# 20.net
KiCad netlist of a schematic drawn in Altium Designer
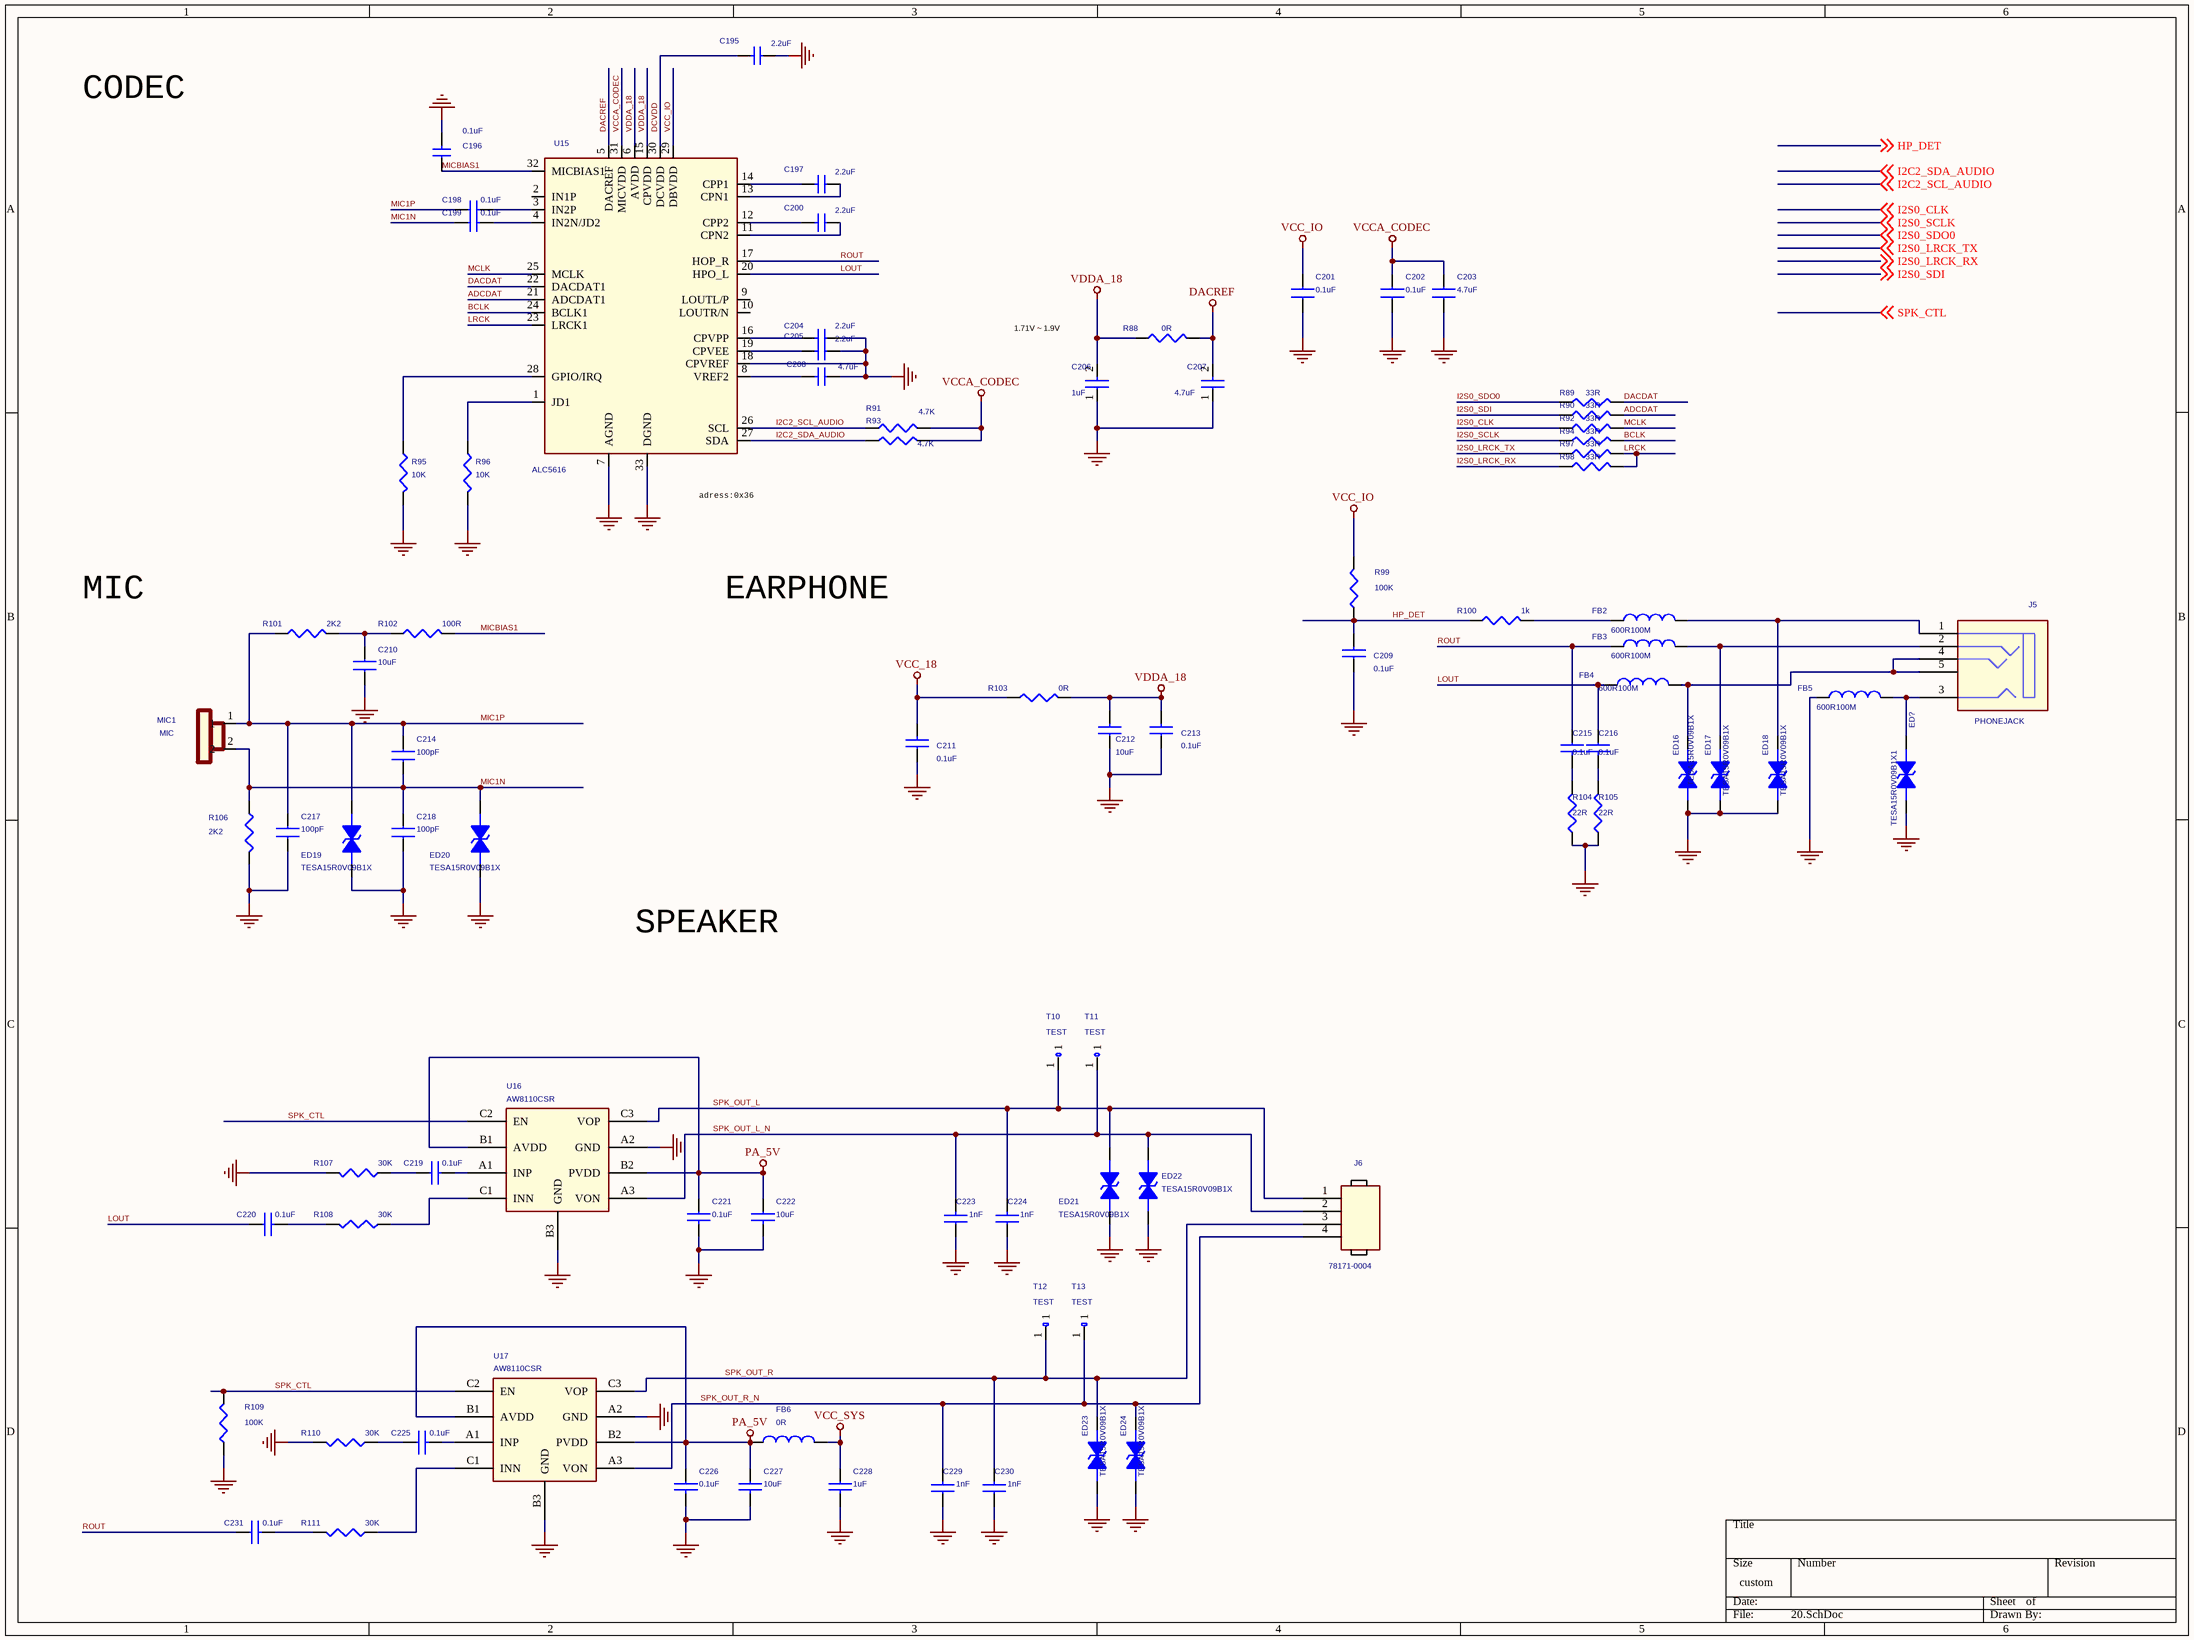
[diagram p0: 20.SchDoc]

(export (version "E")
  (design (tool "Eeschema 10.0.6"))
  (components
    (comp (ref "C195")
      (value "2.2uF")
      (footprint "C0603")
      (description "RoHS CHIP CAP 2.2uF +10/-10% X5R")
      (libsource (lib "*") (part "SMALL CAP"))
    )
    (comp (ref "C196")
      (value "0.1uF")
      (footprint "c0402")
      (description "RoHS CHIP CAP 0.1uF +10/-10% X7R")
      (libsource (lib "*") (part "SMALL CAP"))
    )
    (comp (ref "C197")
      (value "2.2uF")
      (footprint "C0603")
      (description "RoHS CHIP CAP 2.2uF +10/-10% X5R")
      (libsource (lib "*") (part "SMALL CAP"))
    )
    (comp (ref "C198")
      (value "0.1uF")
      (footprint "c0402")
      (description "RoHS CHIP CAP 0.1uF +10/-10% X7R")
      (libsource (lib "*") (part "SMALL CAP"))
    )
    (comp (ref "C199")
      (value "0.1uF")
      (footprint "c0402")
      (description "RoHS CHIP CAP 0.1uF +10/-10% X7R")
      (libsource (lib "*") (part "SMALL CAP"))
    )
    (comp (ref "C200")
      (value "2.2uF")
      (footprint "C0603")
      (description "RoHS CHIP CAP 2.2uF +10/-10% X5R")
      (libsource (lib "*") (part "SMALL CAP"))
    )
    (comp (ref "C201")
      (value "0.1uF")
      (footprint "C0603")
      (description "RoHS CHIP CAP 0.1uF +10/-10% X7R")
      (libsource (lib "*") (part "CAP NP_Dup3"))
    )
    (comp (ref "C202")
      (value "0.1uF")
      (footprint "C0603")
      (description "RoHS CHIP CAP 0.1uF +10/-10% X7R")
      (libsource (lib "*") (part "CAP NP_Dup3"))
    )
    (comp (ref "C203")
      (value "4.7uF")
      (footprint "C0603")
      (description "RoHS CHIP CAP 2.2uF +10/-10% X5R")
      (libsource (lib "*") (part "CAP NP_Dup3"))
    )
    (comp (ref "C204")
      (value "2.2uF")
      (footprint "C0603")
      (description "RoHS CHIP CAP 2.2uF +10/-10% X5R")
      (libsource (lib "*") (part "SMALL CAP"))
    )
    (comp (ref "C205")
      (value "2.2uF")
      (footprint "C0603")
      (description "RoHS CHIP CAP 2.2uF +10/-10% X5R")
      (libsource (lib "*") (part "SMALL CAP"))
    )
    (comp (ref "C206")
      (value "1uF")
      (footprint "c0402")
      (description "RoHS CHIP CAP 4.7uF +10/-10% X5R")
      (libsource (lib "*") (part "CAP NP_0"))
    )
    (comp (ref "C207")
      (value "4.7uF")
      (footprint "C0603")
      (description "RoHS CHIP CAP 4.7uF +10/-10% X5R")
      (libsource (lib "*") (part "CAP NP_0"))
    )
    (comp (ref "C208")
      (value "4.7uF")
      (footprint "C0603")
      (description "RoHS CHIP CAP 4.7uF +10/-10% X5R")
      (libsource (lib "*") (part "SMALL CAP"))
    )
    (comp (ref "C209") (value "0.1uF") (footprint "c0402") (libsource (lib "*") (part "CAP NP_4")))
    (comp (ref "C210") (value "10uF") (footprint "C0603") (libsource (lib "*") (part "CAP NP_Dup3")))
    (comp (ref "C211") (value "0.1uF") (footprint "C0201") (libsource (lib "*") (part "CAP NP_4")))
    (comp (ref "C212") (value "10uF") (footprint "C0603") (libsource (lib "*") (part "CAP NP_4")))
    (comp (ref "C213") (value "0.1uF") (footprint "c0402") (libsource (lib "*") (part "CAP NP_4")))
    (comp (ref "C214")
      (value "100pF")
      (footprint "C0603")
      (description "RoHS CHIP CAP 100pF +10/-10% X7R")
      (libsource (lib "*") (part "CAP NP_Dup3"))
    )
    (comp (ref "C215")
      (value "0.1uF")
      (footprint "c0402")
      (description "RoHS CHIP CAP 0.1uF +10/-10% X7R")
      (libsource (lib "*") (part "CAP NP_Dup1"))
    )
    (comp (ref "C216")
      (value "0.1uF")
      (footprint "c0402")
      (description "RoHS CHIP CAP 0.1uF +10/-10% X7R")
      (libsource (lib "*") (part "CAP NP_Dup1"))
    )
    (comp (ref "C217")
      (value "100pF")
      (footprint "C0603")
      (description "RoHS CHIP CAP 100pF +10/-10% X7R")
      (libsource (lib "*") (part "CAP NP_Dup3"))
    )
    (comp (ref "C218")
      (value "100pF")
      (footprint "C0603")
      (description "RoHS CHIP CAP 100pF +10/-10% X7R")
      (libsource (lib "*") (part "CAP NP_Dup3"))
    )
    (comp (ref "C219")
      (value "0.1uF")
      (footprint "C0402")
      (description "RoHS CHIP CAP 0.1uF +10/-10% X7R")
      (libsource (lib "*") (part "CAP NP_Dup2"))
    )
    (comp (ref "C220")
      (value "0.1uF")
      (footprint "C0402")
      (description "RoHS CHIP CAP 0.1uF +10/-10% X7R")
      (libsource (lib "*") (part "CAP NP_Dup2"))
    )
    (comp (ref "C221")
      (value "0.1uF")
      (footprint "C0402")
      (description "RoHS CHIP CAP 0.1uF +10/-10% X7R")
      (libsource (lib "*") (part "CAP NP_Dup2"))
    )
    (comp (ref "C222")
      (value "10uF")
      (footprint "C0402")
      (description "RoHS CHIP CAP 10uF +10/-10% X5R")
      (libsource (lib "*") (part "CAP NP_Dup2"))
    )
    (comp (ref "C223")
      (value "1nF")
      (footprint "C0402")
      (description "RoHS CHIP CAP 1nF +10/-10% X7R")
      (libsource (lib "*") (part "CAP NP_Dup2"))
    )
    (comp (ref "C224")
      (value "1nF")
      (footprint "C0402")
      (description "RoHS CHIP CAP 1nF +10/-10% X7R")
      (libsource (lib "*") (part "CAP NP_Dup2"))
    )
    (comp (ref "C225")
      (value "0.1uF")
      (footprint "C0402")
      (description "RoHS CHIP CAP 0.1uF +10/-10% X7R")
      (libsource (lib "*") (part "CAP NP_Dup2"))
    )
    (comp (ref "C226")
      (value "0.1uF")
      (footprint "C0402")
      (description "RoHS CHIP CAP 0.1uF +10/-10% X7R")
      (libsource (lib "*") (part "CAP NP_Dup2"))
    )
    (comp (ref "C227")
      (value "10uF")
      (footprint "C0402")
      (description "RoHS CHIP CAP 10uF +10/-10% X5R")
      (libsource (lib "*") (part "CAP NP_Dup2"))
    )
    (comp (ref "C228")
      (value "1uF")
      (footprint "C0402")
      (description "RoHS CHIP CAP 10uF +10/-10% X5R")
      (libsource (lib "*") (part "CAP NP_Dup2"))
    )
    (comp (ref "C229")
      (value "1nF")
      (footprint "C0402")
      (description "RoHS CHIP CAP 1nF +10/-10% X7R")
      (libsource (lib "*") (part "CAP NP_Dup2"))
    )
    (comp (ref "C230")
      (value "1nF")
      (footprint "C0402")
      (description "RoHS CHIP CAP 1nF +10/-10% X7R")
      (libsource (lib "*") (part "CAP NP_Dup2"))
    )
    (comp (ref "C231")
      (value "0.1uF")
      (footprint "C0402")
      (description "RoHS CHIP CAP 0.1uF +10/-10% X7R")
      (libsource (lib "*") (part "CAP NP_Dup2"))
    )
    (comp (ref "ED16")
      (value "TESA15R0V09B1X")
      (footprint "E0402N")
      (description "ESD Component,5V,30P,SMD,0402")
      (libsource (lib "*") (part "TVS"))
    )
    (comp (ref "ED17")
      (value "TESA15R0V09B1X")
      (footprint "E0402N")
      (description "ESD Component,5V,30P,SMD,0402")
      (libsource (lib "*") (part "TVS"))
    )
    (comp (ref "ED18")
      (value "TESA15R0V09B1X")
      (footprint "E0402N")
      (description "ESD Component,5V,30P,SMD,0402")
      (libsource (lib "*") (part "TVS"))
    )
    (comp (ref "ED19")
      (value "TESA15R0V09B1X")
      (footprint "E0201")
      (description "NC/ESD Component,5V,30P,SMD,0402")
      (libsource (lib "*") (part "DIODE BI-DIR TRIG"))
    )
    (comp (ref "ED20")
      (value "TESA15R0V09B1X")
      (footprint "E0201")
      (description "NC/ESD Component,5V,30P,SMD,0402")
      (libsource (lib "*") (part "DIODE BI-DIR TRIG"))
    )
    (comp (ref "ED21")
      (value "TESA15R0V09B1X")
      (footprint "E0201")
      (description "NC/ESD Component,5V,30P,SMD,0402")
      (libsource (lib "*") (part "DIODE BI-DIR TRIG"))
    )
    (comp (ref "ED22")
      (value "TESA15R0V09B1X")
      (footprint "E0201")
      (description "NC/ESD Component,5V,30P,SMD,0402")
      (libsource (lib "*") (part "DIODE BI-DIR TRIG"))
    )
    (comp (ref "ED23")
      (value "TESA15R0V09B1X")
      (footprint "E0402N")
      (description "ESD Component,5V,30P,SMD,0402")
      (libsource (lib "*") (part "TVS"))
    )
    (comp (ref "ED24")
      (value "TESA15R0V09B1X")
      (footprint "E0402N")
      (description "ESD Component,5V,30P,SMD,0402")
      (libsource (lib "*") (part "TVS"))
    )
    (comp (ref "FB2")
      (value "600R100M")
      (footprint "L0402")
      (description "ROHS CHIP RES 33R 1/16W 5%")
      (libsource (lib "*") (part "INDUCTOR_Dup1"))
    )
    (comp (ref "FB3")
      (value "600R100M")
      (footprint "L0402")
      (description "ROHS CHIP RES 33R 1/16W 5%")
      (libsource (lib "*") (part "INDUCTOR_Dup1"))
    )
    (comp (ref "FB4")
      (value "600R100M")
      (footprint "L0402")
      (description "ROHS CHIP RES 33R 1/16W 5%")
      (libsource (lib "*") (part "INDUCTOR_Dup1"))
    )
    (comp (ref "FB5")
      (value "600R100M")
      (footprint "L0402")
      (description "ROHS CHIP RES 33R 1/16W 5%")
      (libsource (lib "*") (part "INDUCTOR_Dup1"))
    )
    (comp (ref "FB6")
      (value "0R")
      (footprint "L0603")
      (description "ROHS CHIP RES 0 Ohm 1/16W +/-5%")
      (libsource (lib "*") (part "INDUCTOR_Dup1"))
    )
    (comp (ref "J5")
      (value "PHONEJACK")
      (footprint "J301R05GA6ZL2")
      (description "耳插")
      (libsource (lib "*") (part "PHONEJACK STEREO SW_0"))
    )
    (comp (ref "J6") (value "78171-0004") (footprint "78171-0004") (libsource (lib "*") (part "HEADER 4")))
    (comp (ref "MIC1") (value "MIC") (footprint "78171-0002") (libsource (lib "*") (part "MIC")))
    (comp (ref "R88")
      (value "0R")
      (footprint "R0402")
      (description "ROHS CHIP RES 0 Ohm 1/16W +/-5%")
      (libsource (lib "*") (part "R"))
    )
    (comp (ref "R89")
      (value "33R")
      (footprint "r0402")
      (description "ROHS CHIP RES 33 Ohm 1/16W +/-5%")
      (libsource (lib "*") (part "R"))
    )
    (comp (ref "R90")
      (value "33R")
      (footprint "r0402")
      (description "ROHS CHIP RES 33 Ohm 1/16W +/-5%")
      (libsource (lib "*") (part "R"))
    )
    (comp (ref "R91")
      (value "4.7K")
      (footprint "r0402")
      (description "ROHS CHIP RES 0 Ohm 1/16W +/-5%")
      (libsource (lib "*") (part "R"))
    )
    (comp (ref "R92")
      (value "33R")
      (footprint "r0402")
      (description "ROHS CHIP RES 33 Ohm 1/16W +/-5%")
      (libsource (lib "*") (part "R"))
    )
    (comp (ref "R93")
      (value "4.7K")
      (footprint "r0402")
      (description "ROHS CHIP RES 0 Ohm 1/16W +/-5%")
      (libsource (lib "*") (part "R"))
    )
    (comp (ref "R94")
      (value "33R")
      (footprint "r0402")
      (description "ROHS CHIP RES 33 Ohm 1/16W +/-5%")
      (libsource (lib "*") (part "R"))
    )
    (comp (ref "R95")
      (value "10K")
      (footprint "r0402")
      (description "ROHS CHIP RES 10K 1/16W +/-5%")
      (libsource (lib "*") (part "RESISTOR"))
    )
    (comp (ref "R96")
      (value "10K")
      (footprint "r0402")
      (description "ROHS CHIP RES 10K 1/16W +/-5%")
      (libsource (lib "*") (part "RESISTOR"))
    )
    (comp (ref "R97")
      (value "33R")
      (footprint "r0402")
      (description "ROHS CHIP RES 33 Ohm 1/16W +/-5%")
      (libsource (lib "*") (part "R"))
    )
    (comp (ref "R98")
      (value "33R")
      (footprint "r0402")
      (description "ROHS CHIP RES 33 Ohm 1/16W +/-5%")
      (libsource (lib "*") (part "R"))
    )
    (comp (ref "R99")
      (value "100K")
      (footprint "r0402")
      (description "RES,thick film,10KOhm,+/-5%,1/16W,SMD0402")
      (libsource (lib "*") (part "RESISTOR_1_Dup2"))
    )
    (comp (ref "R100")
      (value "1k")
      (footprint "r0402")
      (description "RES,thick film,10KOhm,+/-5%,1/16W,SMD0402")
      (libsource (lib "*") (part "RESISTOR_1_Dup2"))
    )
    (comp (ref "R101") (value "2K2") (footprint "r0402") (libsource (lib "*") (part "RESISTOR_0_Dup2")))
    (comp (ref "R102")
      (value "100R")
      (footprint "r0402")
      (description "RES,thick film,10KOhm,+/-5%,1/16W,SMD0402")
      (libsource (lib "*") (part "RESISTOR_1_Dup2"))
    )
    (comp (ref "R103")
      (value "0R")
      (footprint "R0402")
      (description "ROHS CHIP RES 0R 1/16W 5%")
      (libsource (lib "*") (part "RESISTOR"))
    )
    (comp (ref "R104")
      (value "22R")
      (footprint "r0402")
      (description "ROHS CHIP RES 22R 1/16W 5%")
      (libsource (lib "*") (part "RESISTOR"))
    )
    (comp (ref "R105")
      (value "22R")
      (footprint "r0402")
      (description "ROHS CHIP RES 22R 1/16W 5%")
      (libsource (lib "*") (part "RESISTOR"))
    )
    (comp (ref "R106")
      (value "2K2")
      (footprint "r0402")
      (description "贴片电阻")
      (libsource (lib "*") (part "RESISTOR_0_Dup2"))
    )
    (comp (ref "R107")
      (value "30K")
      (footprint "R0402")
      (description "ROHS CHIP RES 30K 1/16W +/-5%")
      (libsource (lib "*") (part "RESISTOR_Dup1"))
    )
    (comp (ref "R108")
      (value "30K")
      (footprint "R0402")
      (description "ROHS CHIP RES 30K 1/16W +/-5%")
      (libsource (lib "*") (part "RESISTOR_Dup1"))
    )
    (comp (ref "R109")
      (value "100K")
      (footprint "r0402")
      (description "RES,thick film,10KOhm,+/-5%,1/16W,SMD0402")
      (libsource (lib "*") (part "RESISTOR_1_Dup2"))
    )
    (comp (ref "R110")
      (value "30K")
      (footprint "R0402")
      (description "ROHS CHIP RES 30K 1/16W +/-5%")
      (libsource (lib "*") (part "RESISTOR_Dup1"))
    )
    (comp (ref "R111")
      (value "30K")
      (footprint "R0402")
      (description "ROHS CHIP RES 30K 1/16W +/-5%")
      (libsource (lib "*") (part "RESISTOR_Dup1"))
    )
    (comp (ref "T10") (value "TEST") (footprint "TEST") (libsource (lib "*") (part "TEST_0")))
    (comp (ref "T11") (value "TEST") (footprint "TEST") (libsource (lib "*") (part "TEST_0")))
    (comp (ref "T12") (value "TEST") (footprint "TEST") (libsource (lib "*") (part "TEST_0")))
    (comp (ref "T13") (value "TEST") (footprint "TEST") (libsource (lib "*") (part "TEST_0")))
    (comp (ref "TESA15R0V09B1X1")
      (value "ED?")
      (footprint "E0402N")
      (description "ESD Component,5V,30P,SMD,0402")
      (libsource (lib "*") (part "TVS"))
    )
    (comp (ref "U15")
      (value "ALC5616")
      (footprint "QFN32")
      (description "CODEC IC")
      (libsource (lib "*") (part "ALC5616"))
    )
    (comp (ref "U16")
      (value "AW8110CSR")
      (footprint "CSP9")
      (description "Class D Audio AMP")
      (libsource (lib "*") (part "LM4990_0"))
    )
    (comp (ref "U17")
      (value "AW8110CSR")
      (footprint "CSP9")
      (description "Class D Audio AMP")
      (libsource (lib "*") (part "LM4990_0"))
    )
  )
  (nets
    (net (code "1") (name "/ADCDAT") (class "Default")
      (node (ref "R90") (pin "2") (pinfunction "2_2") (pintype "passive"))
      (node (ref "U15") (pin "21") (pinfunction "ADCDAT1_21") (pintype "passive"))
    )
    (net (code "2") (name "/BCLK") (class "Default")
      (node (ref "R94") (pin "2") (pinfunction "2_2") (pintype "passive"))
      (node (ref "U15") (pin "24") (pinfunction "BCLK1_24") (pintype "passive"))
    )
    (net (code "3") (name "/DACDAT") (class "Default")
      (node (ref "R89") (pin "2") (pinfunction "2_2") (pintype "passive"))
      (node (ref "U15") (pin "22") (pinfunction "DACDAT1_22") (pintype "passive"))
    )
    (net (code "4") (name "/DCVDD") (class "Default")
      (node (ref "C195") (pin "2") (pinfunction "2_2") (pintype "passive"))
      (node (ref "U15") (pin "30") (pinfunction "DCVDD_30") (pintype "passive"))
    )
    (net (code "5") (name "/LOUT") (class "Default")
      (node (ref "C216") (pin "1") (pinfunction "1_1") (pintype "passive"))
      (node (ref "C220") (pin "1") (pinfunction "1_1") (pintype "passive"))
      (node (ref "FB4") (pin "2") (pinfunction "2_2") (pintype "passive"))
      (node (ref "U15") (pin "20") (pinfunction "HPO_L_20") (pintype "passive"))
    )
    (net (code "6") (name "/LRCK") (class "Default")
      (node (ref "R97") (pin "2") (pinfunction "2_2") (pintype "passive"))
      (node (ref "R98") (pin "2") (pinfunction "2_2") (pintype "passive"))
      (node (ref "U15") (pin "23") (pinfunction "LRCK1_23") (pintype "passive"))
    )
    (net (code "7") (name "/MCLK") (class "Default")
      (node (ref "R92") (pin "2") (pinfunction "2_2") (pintype "passive"))
      (node (ref "U15") (pin "25") (pinfunction "MCLK_25") (pintype "passive"))
    )
    (net (code "8") (name "/MIC1N") (class "Default")
      (node (ref "C199") (pin "1") (pinfunction "1_1") (pintype "passive"))
      (node (ref "C214") (pin "1") (pinfunction "1_1") (pintype "passive"))
      (node (ref "C218") (pin "2") (pinfunction "2_2") (pintype "passive"))
      (node (ref "ED20") (pin "1") (pinfunction "1_1") (pintype "passive"))
      (node (ref "MIC1") (pin "2") (pinfunction "2_2") (pintype "passive"))
      (node (ref "R106") (pin "2") (pinfunction "2_2") (pintype "passive"))
    )
    (net (code "9") (name "/MIC1P") (class "Default")
      (node (ref "C198") (pin "1") (pinfunction "1_1") (pintype "passive"))
      (node (ref "C214") (pin "2") (pinfunction "2_2") (pintype "passive"))
      (node (ref "C217") (pin "2") (pinfunction "2_2") (pintype "passive"))
      (node (ref "ED19") (pin "1") (pinfunction "1_1") (pintype "passive"))
      (node (ref "MIC1") (pin "1") (pinfunction "1_1") (pintype "passive"))
      (node (ref "R101") (pin "1") (pinfunction "1_1") (pintype "passive"))
    )
    (net (code "10") (name "/MICBIAS1") (class "Default")
      (node (ref "C196") (pin "1") (pinfunction "1_1") (pintype "passive"))
      (node (ref "R102") (pin "1") (pinfunction "1_1") (pintype "passive"))
      (node (ref "U15") (pin "32") (pinfunction "MICBIAS1_32") (pintype "passive"))
    )
    (net (code "11") (name "/ROUT") (class "Default")
      (node (ref "C215") (pin "1") (pinfunction "1_1") (pintype "passive"))
      (node (ref "C231") (pin "1") (pinfunction "1_1") (pintype "passive"))
      (node (ref "FB3") (pin "2") (pinfunction "2_2") (pintype "passive"))
      (node (ref "U15") (pin "17") (pinfunction "HOP_R_17") (pintype "passive"))
    )
    (net (code "12") (name "/SPK_OUT_L") (class "Default")
      (node (ref "C224") (pin "2") (pinfunction "2_2") (pintype "passive"))
      (node (ref "ED21") (pin "1") (pinfunction "1_1") (pintype "passive"))
      (node (ref "J6") (pin "1") (pinfunction "1_1") (pintype "passive"))
      (node (ref "T10") (pin "1") (pinfunction "1_1") (pintype "passive"))
      (node (ref "U16") (pin "C3") (pinfunction "VOP_C3") (pintype "passive"))
    )
    (net (code "13") (name "/SPK_OUT_L_N") (class "Default")
      (node (ref "C223") (pin "2") (pinfunction "2_2") (pintype "passive"))
      (node (ref "ED22") (pin "1") (pinfunction "1_1") (pintype "passive"))
      (node (ref "J6") (pin "2") (pinfunction "2_2") (pintype "passive"))
      (node (ref "T11") (pin "1") (pinfunction "1_1") (pintype "passive"))
      (node (ref "U16") (pin "A3") (pinfunction "VON_A3") (pintype "passive"))
    )
    (net (code "14") (name "/SPK_OUT_R") (class "Default")
      (node (ref "C230") (pin "2") (pinfunction "2_2") (pintype "passive"))
      (node (ref "ED23") (pin "1") (pinfunction "1_1") (pintype "passive"))
      (node (ref "J6") (pin "3") (pinfunction "3_3") (pintype "passive"))
      (node (ref "T12") (pin "1") (pinfunction "1_1") (pintype "passive"))
      (node (ref "U17") (pin "C3") (pinfunction "VOP_C3") (pintype "passive"))
    )
    (net (code "15") (name "/SPK_OUT_R_N") (class "Default")
      (node (ref "C229") (pin "2") (pinfunction "2_2") (pintype "passive"))
      (node (ref "ED24") (pin "1") (pinfunction "1_1") (pintype "passive"))
      (node (ref "J6") (pin "4") (pinfunction "4_4") (pintype "passive"))
      (node (ref "T13") (pin "1") (pinfunction "1_1") (pintype "passive"))
      (node (ref "U17") (pin "A3") (pinfunction "VON_A3") (pintype "passive"))
    )
    (net (code "16") (name "DACREF") (class "Default")
      (node (ref "C207") (pin "2") (pinfunction "2_2") (pintype "passive"))
      (node (ref "R88") (pin "2") (pinfunction "2_2") (pintype "passive"))
      (node (ref "U15") (pin "5") (pinfunction "DACREF_5") (pintype "passive"))
    )
    (net (code "17") (name "GND") (class "Default")
      (node (ref "C195") (pin "1") (pinfunction "1_1") (pintype "passive"))
      (node (ref "C196") (pin "2") (pinfunction "2_2") (pintype "passive"))
      (node (ref "C201") (pin "1") (pinfunction "1_1") (pintype "passive"))
      (node (ref "C202") (pin "1") (pinfunction "1_1") (pintype "passive"))
      (node (ref "C203") (pin "1") (pinfunction "1_1") (pintype "passive"))
      (node (ref "C204") (pin "1") (pinfunction "1_1") (pintype "passive"))
      (node (ref "C205") (pin "1") (pinfunction "1_1") (pintype "passive"))
      (node (ref "C206") (pin "1") (pinfunction "1_1") (pintype "passive"))
      (node (ref "C207") (pin "1") (pinfunction "1_1") (pintype "passive"))
      (node (ref "C208") (pin "1") (pinfunction "1_1") (pintype "passive"))
      (node (ref "C209") (pin "1") (pinfunction "1_1") (pintype "passive"))
      (node (ref "C210") (pin "1") (pinfunction "1_1") (pintype "passive"))
      (node (ref "C211") (pin "1") (pinfunction "1_1") (pintype "passive"))
      (node (ref "C212") (pin "1") (pinfunction "1_1") (pintype "passive"))
      (node (ref "C213") (pin "1") (pinfunction "1_1") (pintype "passive"))
      (node (ref "C217") (pin "1") (pinfunction "1_1") (pintype "passive"))
      (node (ref "C218") (pin "1") (pinfunction "1_1") (pintype "passive"))
      (node (ref "C221") (pin "2") (pinfunction "2_2") (pintype "passive"))
      (node (ref "C222") (pin "2") (pinfunction "2_2") (pintype "passive"))
      (node (ref "C223") (pin "1") (pinfunction "1_1") (pintype "passive"))
      (node (ref "C224") (pin "1") (pinfunction "1_1") (pintype "passive"))
      (node (ref "C226") (pin "2") (pinfunction "2_2") (pintype "passive"))
      (node (ref "C227") (pin "2") (pinfunction "2_2") (pintype "passive"))
      (node (ref "C228") (pin "2") (pinfunction "2_2") (pintype "passive"))
      (node (ref "C229") (pin "1") (pinfunction "1_1") (pintype "passive"))
      (node (ref "C230") (pin "1") (pinfunction "1_1") (pintype "passive"))
      (node (ref "ED16") (pin "2") (pinfunction "2_2") (pintype "passive"))
      (node (ref "ED17") (pin "2") (pinfunction "2_2") (pintype "passive"))
      (node (ref "ED18") (pin "2") (pinfunction "2_2") (pintype "passive"))
      (node (ref "ED19") (pin "2") (pinfunction "2_2") (pintype "passive"))
      (node (ref "ED20") (pin "2") (pinfunction "2_2") (pintype "passive"))
      (node (ref "ED21") (pin "2") (pinfunction "2_2") (pintype "passive"))
      (node (ref "ED22") (pin "2") (pinfunction "2_2") (pintype "passive"))
      (node (ref "ED23") (pin "2") (pinfunction "2_2") (pintype "passive"))
      (node (ref "ED24") (pin "2") (pinfunction "2_2") (pintype "passive"))
      (node (ref "FB5") (pin "2") (pinfunction "2_2") (pintype "passive"))
      (node (ref "R104") (pin "1") (pinfunction "1_1") (pintype "passive"))
      (node (ref "R105") (pin "1") (pinfunction "1_1") (pintype "passive"))
      (node (ref "R106") (pin "1") (pinfunction "1_1") (pintype "passive"))
      (node (ref "R107") (pin "2") (pinfunction "2_2") (pintype "passive"))
      (node (ref "R109") (pin "2") (pinfunction "2_2") (pintype "passive"))
      (node (ref "R110") (pin "2") (pinfunction "2_2") (pintype "passive"))
      (node (ref "R95") (pin "1") (pinfunction "1_1") (pintype "passive"))
      (node (ref "R96") (pin "1") (pinfunction "1_1") (pintype "passive"))
      (node (ref "TESA15R0V09B1X1") (pin "2") (pinfunction "2_2") (pintype "passive"))
      (node (ref "U15") (pin "18") (pinfunction "CPVREF_18") (pintype "passive"))
      (node (ref "U15") (pin "33") (pinfunction "DGND_33") (pintype "passive"))
      (node (ref "U15") (pin "7") (pinfunction "AGND_7") (pintype "passive"))
      (node (ref "U16") (pin "A2") (pinfunction "GND_A2") (pintype "power_in"))
      (node (ref "U16") (pin "B3") (pinfunction "GND_B3") (pintype "power_in"))
      (node (ref "U17") (pin "A2") (pinfunction "GND_A2") (pintype "power_in"))
      (node (ref "U17") (pin "B3") (pinfunction "GND_B3") (pintype "power_in"))
    )
    (net (code "18") (name "HP_DET") (class "Default")
      (node (ref "C209") (pin "2") (pinfunction "2_2") (pintype "passive"))
      (node (ref "R100") (pin "2") (pinfunction "2_2") (pintype "passive"))
      (node (ref "R99") (pin "2") (pinfunction "2_2") (pintype "passive"))
    )
    (net (code "19") (name "I2C2_SCL_AUDIO") (class "Default")
      (node (ref "R91") (pin "1") (pinfunction "1_1") (pintype "passive"))
      (node (ref "U15") (pin "26") (pinfunction "SCL_26") (pintype "passive"))
    )
    (net (code "20") (name "I2C2_SDA_AUDIO") (class "Default")
      (node (ref "R93") (pin "1") (pinfunction "1_1") (pintype "passive"))
      (node (ref "U15") (pin "27") (pinfunction "SDA_27") (pintype "passive"))
    )
    (net (code "21") (name "I2S0_CLK") (class "Default")
      (node (ref "R92") (pin "1") (pinfunction "1_1") (pintype "passive"))
    )
    (net (code "22") (name "I2S0_LRCK_RX") (class "Default")
      (node (ref "R98") (pin "1") (pinfunction "1_1") (pintype "passive"))
    )
    (net (code "23") (name "I2S0_LRCK_TX") (class "Default")
      (node (ref "R97") (pin "1") (pinfunction "1_1") (pintype "passive"))
    )
    (net (code "24") (name "I2S0_SCLK") (class "Default")
      (node (ref "R94") (pin "1") (pinfunction "1_1") (pintype "passive"))
    )
    (net (code "25") (name "I2S0_SDI") (class "Default")
      (node (ref "R90") (pin "1") (pinfunction "1_1") (pintype "passive"))
    )
    (net (code "26") (name "I2S0_SDO0") (class "Default")
      (node (ref "R89") (pin "1") (pinfunction "1_1") (pintype "passive"))
    )
    (net (code "27") (name "Net-(C210-Pad2)") (class "Default")
      (node (ref "C210") (pin "2") (pinfunction "2_2") (pintype "passive"))
      (node (ref "R101") (pin "2") (pinfunction "2_2") (pintype "passive"))
      (node (ref "R102") (pin "2") (pinfunction "2_2") (pintype "passive"))
    )
    (net (code "28") (name "Net-(C215-Pad2)") (class "Default")
      (node (ref "C215") (pin "2") (pinfunction "2_2") (pintype "passive"))
      (node (ref "R104") (pin "2") (pinfunction "2_2") (pintype "passive"))
    )
    (net (code "29") (name "Net-(C216-Pad2)") (class "Default")
      (node (ref "C216") (pin "2") (pinfunction "2_2") (pintype "passive"))
      (node (ref "R105") (pin "2") (pinfunction "2_2") (pintype "passive"))
    )
    (net (code "30") (name "Net-(C219-Pad1)") (class "Default")
      (node (ref "C219") (pin "1") (pinfunction "1_1") (pintype "passive"))
      (node (ref "R107") (pin "1") (pinfunction "1_1") (pintype "passive"))
    )
    (net (code "31") (name "Net-(C220-Pad2)") (class "Default")
      (node (ref "C220") (pin "2") (pinfunction "2_2") (pintype "passive"))
      (node (ref "R108") (pin "2") (pinfunction "2_2") (pintype "passive"))
    )
    (net (code "32") (name "Net-(C225-Pad1)") (class "Default")
      (node (ref "C225") (pin "1") (pinfunction "1_1") (pintype "passive"))
      (node (ref "R110") (pin "1") (pinfunction "1_1") (pintype "passive"))
    )
    (net (code "33") (name "Net-(C231-Pad2)") (class "Default")
      (node (ref "C231") (pin "2") (pinfunction "2_2") (pintype "passive"))
      (node (ref "R111") (pin "2") (pinfunction "2_2") (pintype "passive"))
    )
    (net (code "34") (name "Net-(FB2-Pad2)") (class "Default")
      (node (ref "FB2") (pin "2") (pinfunction "2_2") (pintype "passive"))
      (node (ref "R100") (pin "1") (pinfunction "1_1") (pintype "passive"))
    )
    (net (code "35") (name "Net-(J5-D)") (class "Default")
      (node (ref "ED17") (pin "1") (pinfunction "1_1") (pintype "passive"))
      (node (ref "FB3") (pin "1") (pinfunction "1_1") (pintype "passive"))
      (node (ref "J5") (pin "2") (pinfunction "D_2") (pintype "passive"))
    )
    (net (code "36") (name "Net-(J5-HP)") (class "Default")
      (node (ref "ED18") (pin "1") (pinfunction "1_1") (pintype "passive"))
      (node (ref "FB2") (pin "1") (pinfunction "1_1") (pintype "passive"))
      (node (ref "J5") (pin "1") (pinfunction "HP_1") (pintype "passive"))
    )
    (net (code "37") (name "Net-(J5-L)") (class "Default")
      (node (ref "ED16") (pin "1") (pinfunction "1_1") (pintype "passive"))
      (node (ref "FB4") (pin "1") (pinfunction "1_1") (pintype "passive"))
      (node (ref "J5") (pin "4") (pinfunction "R_4") (pintype "passive"))
      (node (ref "J5") (pin "5") (pinfunction "L_5") (pintype "passive"))
    )
    (net (code "38") (name "Net-(J5-R1)") (class "Default")
      (node (ref "FB5") (pin "1") (pinfunction "1_1") (pintype "passive"))
      (node (ref "J5") (pin "3") (pinfunction "R1_3") (pintype "passive"))
      (node (ref "TESA15R0V09B1X1") (pin "1") (pinfunction "1_1") (pintype "passive"))
    )
    (net (code "39") (name "Net-(U15-CPN1)") (class "Default")
      (node (ref "C197") (pin "1") (pinfunction "1_1") (pintype "passive"))
      (node (ref "U15") (pin "13") (pinfunction "CPN1_13") (pintype "passive"))
    )
    (net (code "40") (name "Net-(U15-CPN2)") (class "Default")
      (node (ref "C200") (pin "1") (pinfunction "1_1") (pintype "passive"))
      (node (ref "U15") (pin "11") (pinfunction "CPN2_11") (pintype "passive"))
    )
    (net (code "41") (name "Net-(U15-CPP1)") (class "Default")
      (node (ref "C197") (pin "2") (pinfunction "2_2") (pintype "passive"))
      (node (ref "U15") (pin "14") (pinfunction "CPP1_14") (pintype "passive"))
    )
    (net (code "42") (name "Net-(U15-CPP2)") (class "Default")
      (node (ref "C200") (pin "2") (pinfunction "2_2") (pintype "passive"))
      (node (ref "U15") (pin "12") (pinfunction "CPP2_12") (pintype "passive"))
    )
    (net (code "43") (name "Net-(U15-CPVEE)") (class "Default")
      (node (ref "C205") (pin "2") (pinfunction "2_2") (pintype "passive"))
      (node (ref "U15") (pin "19") (pinfunction "CPVEE_19") (pintype "passive"))
    )
    (net (code "44") (name "Net-(U15-CPVPP)") (class "Default")
      (node (ref "C204") (pin "2") (pinfunction "2_2") (pintype "passive"))
      (node (ref "U15") (pin "16") (pinfunction "CPVPP_16") (pintype "passive"))
    )
    (net (code "45") (name "Net-(U15-GPIO{slash}IRQ)") (class "Default")
      (node (ref "R95") (pin "2") (pinfunction "2_2") (pintype "passive"))
      (node (ref "U15") (pin "28") (pinfunction "GPIO/IRQ_28") (pintype "passive"))
    )
    (net (code "46") (name "Net-(U15-IN2N{slash}JD2)") (class "Default")
      (node (ref "C199") (pin "2") (pinfunction "2_2") (pintype "passive"))
      (node (ref "U15") (pin "4") (pinfunction "IN2N/JD2_4") (pintype "passive"))
    )
    (net (code "47") (name "Net-(U15-IN2P)") (class "Default")
      (node (ref "C198") (pin "2") (pinfunction "2_2") (pintype "passive"))
      (node (ref "U15") (pin "3") (pinfunction "IN2P_3") (pintype "passive"))
    )
    (net (code "48") (name "Net-(U15-JD1)") (class "Default")
      (node (ref "R96") (pin "2") (pinfunction "2_2") (pintype "passive"))
      (node (ref "U15") (pin "1") (pinfunction "JD1_1") (pintype "passive"))
    )
    (net (code "49") (name "Net-(U15-VREF2)") (class "Default")
      (node (ref "C208") (pin "2") (pinfunction "2_2") (pintype "passive"))
      (node (ref "U15") (pin "8") (pinfunction "VREF2_8") (pintype "passive"))
    )
    (net (code "50") (name "Net-(U16-INN)") (class "Default")
      (node (ref "R108") (pin "1") (pinfunction "1_1") (pintype "passive"))
      (node (ref "U16") (pin "C1") (pinfunction "INN_C1") (pintype "passive"))
    )
    (net (code "51") (name "Net-(U16-INP)") (class "Default")
      (node (ref "C219") (pin "2") (pinfunction "2_2") (pintype "passive"))
      (node (ref "U16") (pin "A1") (pinfunction "INP_A1") (pintype "passive"))
    )
    (net (code "52") (name "Net-(U17-INN)") (class "Default")
      (node (ref "R111") (pin "1") (pinfunction "1_1") (pintype "passive"))
      (node (ref "U17") (pin "C1") (pinfunction "INN_C1") (pintype "passive"))
    )
    (net (code "53") (name "Net-(U17-INP)") (class "Default")
      (node (ref "C225") (pin "2") (pinfunction "2_2") (pintype "passive"))
      (node (ref "U17") (pin "A1") (pinfunction "INP_A1") (pintype "passive"))
    )
    (net (code "54") (name "PA_5V") (class "Default")
      (node (ref "C221") (pin "1") (pinfunction "1_1") (pintype "passive"))
      (node (ref "C222") (pin "1") (pinfunction "1_1") (pintype "passive"))
      (node (ref "C226") (pin "1") (pinfunction "1_1") (pintype "passive"))
      (node (ref "C227") (pin "1") (pinfunction "1_1") (pintype "passive"))
      (node (ref "FB6") (pin "2") (pinfunction "2_2") (pintype "passive"))
      (node (ref "U16") (pin "B1") (pinfunction "AVDD_B1") (pintype "passive"))
      (node (ref "U16") (pin "B2") (pinfunction "PVDD_B2") (pintype "passive"))
      (node (ref "U17") (pin "B1") (pinfunction "AVDD_B1") (pintype "passive"))
      (node (ref "U17") (pin "B2") (pinfunction "PVDD_B2") (pintype "passive"))
    )
    (net (code "55") (name "SPK_CTL") (class "Default")
      (node (ref "R109") (pin "1") (pinfunction "1_1") (pintype "passive"))
      (node (ref "U16") (pin "C2") (pinfunction "EN_C2") (pintype "passive"))
      (node (ref "U17") (pin "C2") (pinfunction "EN_C2") (pintype "passive"))
    )
    (net (code "56") (name "VCCA_CODEC") (class "Default")
      (node (ref "C202") (pin "2") (pinfunction "2_2") (pintype "passive"))
      (node (ref "C203") (pin "2") (pinfunction "2_2") (pintype "passive"))
      (node (ref "R91") (pin "2") (pinfunction "2_2") (pintype "passive"))
      (node (ref "R93") (pin "2") (pinfunction "2_2") (pintype "passive"))
      (node (ref "U15") (pin "31") (pinfunction "MICVDD_31") (pintype "passive"))
    )
    (net (code "57") (name "VCC_18") (class "Default")
      (node (ref "C211") (pin "2") (pinfunction "2_2") (pintype "passive"))
      (node (ref "R103") (pin "1") (pinfunction "1_1") (pintype "passive"))
    )
    (net (code "58") (name "VCC_IO") (class "Default")
      (node (ref "C201") (pin "2") (pinfunction "2_2") (pintype "passive"))
      (node (ref "R99") (pin "1") (pinfunction "1_1") (pintype "passive"))
      (node (ref "U15") (pin "29") (pinfunction "DBVDD_29") (pintype "passive"))
    )
    (net (code "59") (name "VCC_SYS") (class "Default")
      (node (ref "C228") (pin "1") (pinfunction "1_1") (pintype "passive"))
      (node (ref "FB6") (pin "1") (pinfunction "1_1") (pintype "passive"))
    )
    (net (code "60") (name "VDDA_18") (class "Default")
      (node (ref "C206") (pin "2") (pinfunction "2_2") (pintype "passive"))
      (node (ref "C212") (pin "2") (pinfunction "2_2") (pintype "passive"))
      (node (ref "C213") (pin "2") (pinfunction "2_2") (pintype "passive"))
      (node (ref "R103") (pin "2") (pinfunction "2_2") (pintype "passive"))
      (node (ref "R88") (pin "1") (pinfunction "1_1") (pintype "passive"))
      (node (ref "U15") (pin "15") (pinfunction "CPVDD_15") (pintype "passive"))
      (node (ref "U15") (pin "6") (pinfunction "AVDD_6") (pintype "passive"))
    )
    (net (code "61") (name "unconnected-(U15-IN1P-Pad2)") (class "Default")
      (node (ref "U15") (pin "2") (pinfunction "IN1P_2") (pintype "passive"))
    )
    (net (code "62") (name "unconnected-(U15-LOUTL{slash}P-Pad9)") (class "Default")
      (node (ref "U15") (pin "9") (pinfunction "LOUTL/P_9") (pintype "passive"))
    )
    (net (code "63") (name "unconnected-(U15-LOUTR{slash}N-Pad10)") (class "Default")
      (node (ref "U15") (pin "10") (pinfunction "LOUTR/N_10") (pintype "passive"))
    )
  )
)
